# UART_Iso.net
KiCad netlist of a schematic drawn in EAGLE
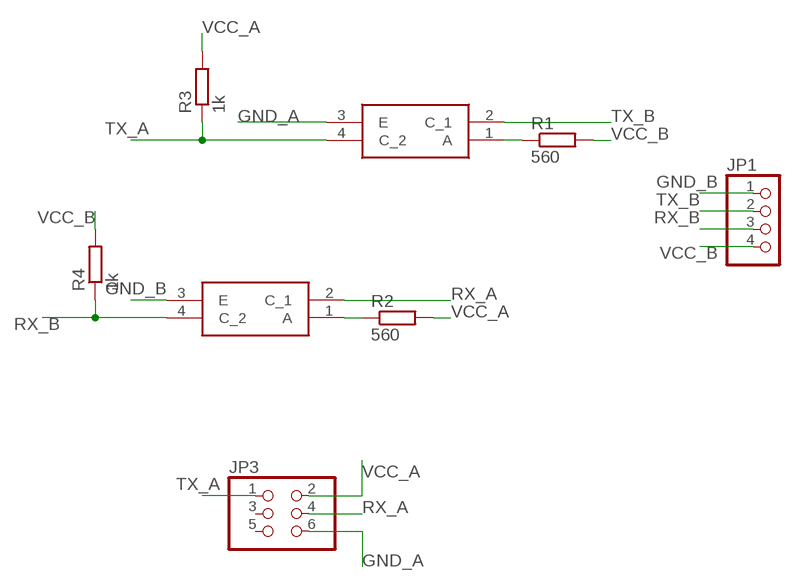
[diagram p0: schematic, sheet 1]

(export (version "E")
  (design (tool "Eeschema 10.0.6"))
  (components
    (comp (ref "JP1")
      (value "PINHD-1X4/90")
      (footprint "eagle-import:1X04_90")
      (libsource (lib "eagle-import") (part "PINHD-1X4/90"))
    )
    (comp (ref "JP3")
      (value "PINHD-2X3")
      (footprint "eagle-import:2X03")
      (libsource (lib "eagle-import") (part "PINHD-2X3"))
    )
    (comp (ref "Q1")
      (value "SFH6186-5T")
      (footprint "eagle-import:SOP254P978X406-4N")
      (fields (field (name "MOUSER_PART_NUMBER") "782-SFH6186-5T"))
      (libsource (lib "eagle-import") (part "SFH6186-5T"))
    )
    (comp (ref "Q2")
      (value "SFH6186-5T")
      (footprint "eagle-import:SOP254P978X406-4N")
      (fields (field (name "MOUSER_PART_NUMBER") "782-SFH6186-5T"))
      (libsource (lib "eagle-import") (part "SFH6186-5T"))
    )
    (comp (ref "R1")
      (value "560")
      (footprint "eagle-import:R0805")
      (libsource (lib "eagle-import") (part "R-EU_R0805"))
    )
    (comp (ref "R2")
      (value "560")
      (footprint "eagle-import:R0805")
      (libsource (lib "eagle-import") (part "R-EU_R0805"))
    )
    (comp (ref "R3")
      (value "1k")
      (footprint "eagle-import:R0805")
      (libsource (lib "eagle-import") (part "R-EU_R0805"))
    )
    (comp (ref "R4")
      (value "1k")
      (footprint "eagle-import:R0805")
      (libsource (lib "eagle-import") (part "R-EU_R0805"))
    )
  )
  (nets
    (net (code "1") (name "/GND_A") (class "Default")
      (node (ref "JP3") (pin "6") (pinfunction "6_6") (pintype "passive"))
      (node (ref "Q2") (pin "3") (pinfunction "E_3") (pintype "bidirectional"))
    )
    (net (code "2") (name "/GND_B") (class "Default")
      (node (ref "JP1") (pin "1") (pinfunction "1_1") (pintype "passive"))
      (node (ref "Q1") (pin "3") (pinfunction "E_3") (pintype "bidirectional"))
    )
    (net (code "3") (name "/RX_A") (class "Default")
      (node (ref "JP3") (pin "4") (pinfunction "4_4") (pintype "passive"))
      (node (ref "Q1") (pin "2") (pinfunction "C_1_2") (pintype "bidirectional"))
    )
    (net (code "4") (name "/RX_B") (class "Default")
      (node (ref "JP1") (pin "3") (pinfunction "3_3") (pintype "passive"))
      (node (ref "Q1") (pin "4") (pinfunction "C_2_4") (pintype "bidirectional"))
      (node (ref "R4") (pin "1") (pinfunction "1_1") (pintype "passive"))
    )
    (net (code "5") (name "/TX_A") (class "Default")
      (node (ref "JP3") (pin "1") (pinfunction "1_1") (pintype "passive"))
      (node (ref "Q2") (pin "4") (pinfunction "C_2_4") (pintype "bidirectional"))
      (node (ref "R3") (pin "1") (pinfunction "1_1") (pintype "passive"))
    )
    (net (code "6") (name "/TX_B") (class "Default")
      (node (ref "JP1") (pin "2") (pinfunction "2_2") (pintype "passive"))
      (node (ref "Q2") (pin "2") (pinfunction "C_1_2") (pintype "bidirectional"))
    )
    (net (code "7") (name "/VCC_A") (class "Default")
      (node (ref "JP3") (pin "2") (pinfunction "2_2") (pintype "passive"))
      (node (ref "R2") (pin "2") (pinfunction "2_2") (pintype "passive"))
      (node (ref "R3") (pin "2") (pinfunction "2_2") (pintype "passive"))
    )
    (net (code "8") (name "/VCC_B") (class "Default")
      (node (ref "JP1") (pin "4") (pinfunction "4_4") (pintype "passive"))
      (node (ref "R1") (pin "2") (pinfunction "2_2") (pintype "passive"))
      (node (ref "R4") (pin "2") (pinfunction "2_2") (pintype "passive"))
    )
    (net (code "9") (name "Net-(Q1-A)") (class "Default")
      (node (ref "Q1") (pin "1") (pinfunction "A_1") (pintype "bidirectional"))
      (node (ref "R2") (pin "1") (pinfunction "1_1") (pintype "passive"))
    )
    (net (code "10") (name "Net-(Q2-A)") (class "Default")
      (node (ref "Q2") (pin "1") (pinfunction "A_1") (pintype "bidirectional"))
      (node (ref "R1") (pin "1") (pinfunction "1_1") (pintype "passive"))
    )
    (net (code "11") (name "unconnected-(JP3-Pad3)") (class "Default")
      (node (ref "JP3") (pin "3") (pinfunction "3_3") (pintype "passive"))
    )
    (net (code "12") (name "unconnected-(JP3-Pad5)") (class "Default")
      (node (ref "JP3") (pin "5") (pinfunction "5_5") (pintype "passive"))
    )
  )
)
